# MIAN.net
KiCad netlist of a schematic drawn in Altium Designer
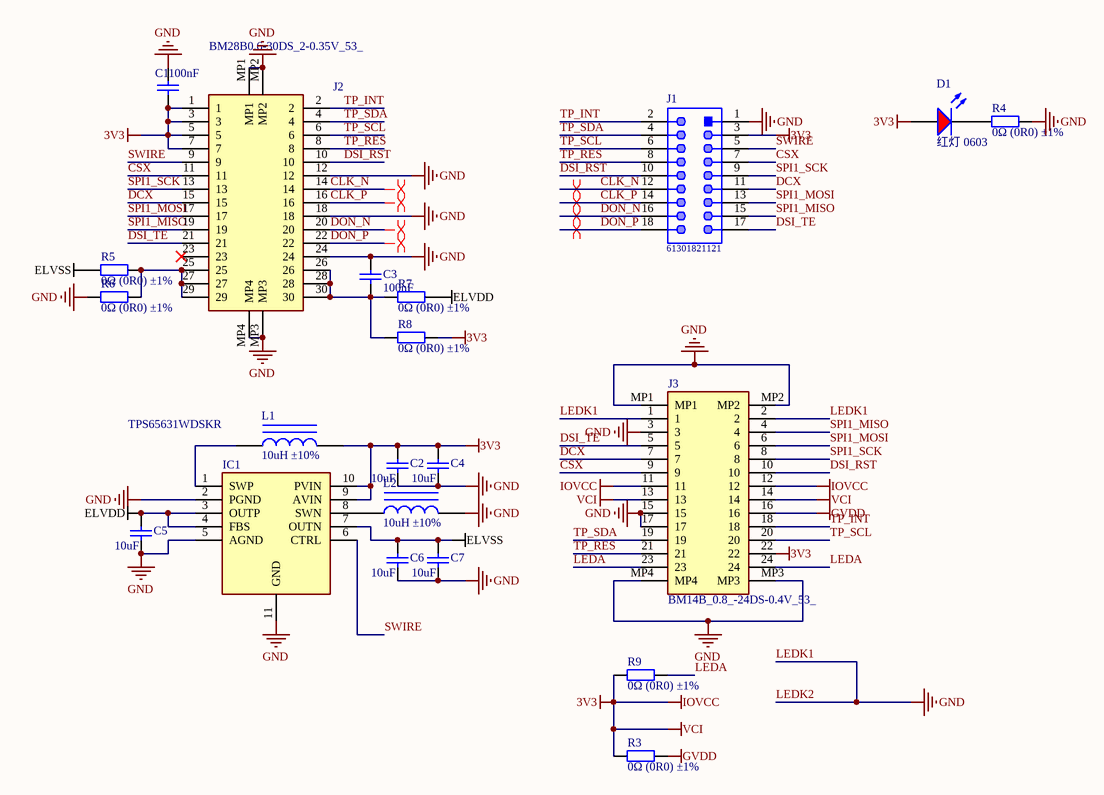
[diagram p0: MIAN.SchDoc]

(export (version "E")
  (design (tool "Eeschema 10.0.6"))
  (components
    (comp (ref "C1")
      (value "100nF")
      (footprint "0402_C")
      (description "Capacitor")
      (fields (field (name "PUBLISHER") "Altium Limited"))
      (libsource (lib "Miscellaneous Devices") (part "CAP"))
    )
    (comp (ref "C2")
      (value "10uF")
      (footprint "0402_C")
      (description "贴片电容")
      (libsource (lib "Miscellaneous Devices LC") (part "0402 10uF (106) 20% 6.3V"))
    )
    (comp (ref "C3")
      (value "100nF")
      (footprint "0402_C")
      (description "Capacitor")
      (fields (field (name "PUBLISHER") "Altium Limited"))
      (libsource (lib "Miscellaneous Devices") (part "CAP"))
    )
    (comp (ref "C4")
      (value "10uF")
      (footprint "0402_C")
      (description "贴片电容")
      (libsource (lib "Miscellaneous Devices LC") (part "0402 10uF (106) 20% 6.3V"))
    )
    (comp (ref "C5")
      (value "10uF")
      (footprint "0402_C")
      (description "贴片电容")
      (libsource (lib "Miscellaneous Devices LC") (part "0402 10uF (106) 20% 6.3V"))
    )
    (comp (ref "C6")
      (value "10uF")
      (footprint "0402_C")
      (description "贴片电容")
      (libsource (lib "Miscellaneous Devices LC") (part "0402 10uF (106) 20% 6.3V"))
    )
    (comp (ref "C7")
      (value "10uF")
      (footprint "0402_C")
      (description "贴片电容")
      (libsource (lib "Miscellaneous Devices LC") (part "0402 10uF (106) 20% 6.3V"))
    )
    (comp (ref "D1")
      (value "红灯 0603")
      (footprint "0603_LED_S1")
      (description "发光二极管")
      (libsource (lib "Miscellaneous Devices LC") (part "0603 红灯"))
    )
    (comp (ref "IC1")
      (value "TPS65631WDSKR")
      (footprint "SamacSys:SON50P250X250X80-11N-D")
      (description "Integrated Circuit")
      (fields (field (name "MOUSER PART NUMBER") "595-TPS65631WDSKR"))
      (libsource (lib "*") (part "TPS65631WDSKR"))
    )
    (comp (ref "J1")
      (value "61301821121")
      (footprint "61301821121")
      (description "THT Vertical Pin Header WR-PHD, Pitch 2.54 mm, Dual Row, 18 pins")
      (fields (field (name "MANUFACTURER") "Wurth Elektronik") (field (name "PUBLISHER") "WurthElektronik"))
      (libsource (lib "Altium Content Vault") (part "WE-CN-2P-M-R18"))
    )
    (comp (ref "J2")
      (value "BM28B0.6-30DS_2-0.35V_53_")
      (footprint "SamacSys:BM28B0630DS2035V53")
      (description "Connector")
      (fields
        (field (name "MANUFACTURER_PART_NUMBER") "BM28B0.6-30DS/2-0.35V(53)")
        (field (name "MOUSER PART NUMBER") "798-28B0630DS2035V53")
      )
      (libsource (lib "*") (part "BM28B0.6-30DS_2-0.35V_53_"))
    )
    (comp (ref "J3")
      (value "BM14B_0.8_-24DS-0.4V_53_")
      (footprint "SamacSys:BM14B0824DS04V53")
      (description "Connector")
      (fields
        (field (name "MANUFACTURER_PART_NUMBER") "BM14B(0.8)-24DS-0.4V(53)")
        (field (name "MOUSER PART NUMBER") "798-BM14B0824DS04V53")
      )
      (libsource (lib "*") (part "BM14B_0.8_-24DS-0.4V_53_"))
    )
    (comp (ref "L1")
      (value "10uH ±10%")
      (footprint "0805_L")
      (description "贴片电感")
      (libsource (lib "Miscellaneous Devices LC") (part "0805 10uH 10%"))
    )
    (comp (ref "L2")
      (value "10uH ±10%")
      (footprint "0805_L")
      (description "贴片电感")
      (libsource (lib "Miscellaneous Devices LC") (part "0805 10uH 10%"))
    )
    (comp (ref "R3")
      (value "0Ω (0R0) ±1%")
      (footprint "0402_R")
      (description "贴片电阻")
      (libsource (lib "Miscellaneous Devices LC") (part "0402 0Ω (0R0) 1%"))
    )
    (comp (ref "R4")
      (value "0Ω (0R0) ±1%")
      (footprint "0402_R")
      (description "贴片电阻")
      (libsource (lib "Miscellaneous Devices LC") (part "0402 0Ω (0R0) 1%"))
    )
    (comp (ref "R5")
      (value "0Ω (0R0) ±1%")
      (footprint "0402_R")
      (description "贴片电阻")
      (libsource (lib "Miscellaneous Devices LC") (part "0402 0Ω (0R0) 1%"))
    )
    (comp (ref "R6")
      (value "0Ω (0R0) ±1%")
      (footprint "0402_R")
      (description "贴片电阻")
      (libsource (lib "Miscellaneous Devices LC") (part "0402 0Ω (0R0) 1%"))
    )
    (comp (ref "R7")
      (value "0Ω (0R0) ±1%")
      (footprint "0402_R")
      (description "贴片电阻")
      (libsource (lib "Miscellaneous Devices LC") (part "0402 0Ω (0R0) 1%"))
    )
    (comp (ref "R8")
      (value "0Ω (0R0) ±1%")
      (footprint "0402_R")
      (description "贴片电阻")
      (libsource (lib "Miscellaneous Devices LC") (part "0402 0Ω (0R0) 1%"))
    )
    (comp (ref "R9")
      (value "0Ω (0R0) ±1%")
      (footprint "0402_R")
      (description "贴片电阻")
      (libsource (lib "Miscellaneous Devices LC") (part "0402 0Ω (0R0) 1%"))
    )
  )
  (nets
    (net (code "1") (name "/CLK_N") (class "Default")
      (node (ref "J1") (pin "12") (pinfunction "12_12") (pintype "passive"))
      (node (ref "J2") (pin "14") (pinfunction "14_14") (pintype "passive"))
    )
    (net (code "2") (name "/CLK_P") (class "Default")
      (node (ref "J1") (pin "14") (pinfunction "14_14") (pintype "passive"))
      (node (ref "J2") (pin "16") (pinfunction "16_16") (pintype "passive"))
    )
    (net (code "3") (name "/CSX") (class "Default")
      (node (ref "J1") (pin "7") (pinfunction "7_7") (pintype "passive"))
      (node (ref "J2") (pin "11") (pinfunction "11_11") (pintype "passive"))
      (node (ref "J3") (pin "9") (pinfunction "9_9") (pintype "passive"))
    )
    (net (code "4") (name "/DCX") (class "Default")
      (node (ref "J1") (pin "11") (pinfunction "11_11") (pintype "passive"))
      (node (ref "J2") (pin "15") (pinfunction "15_15") (pintype "passive"))
      (node (ref "J3") (pin "7") (pinfunction "7_7") (pintype "passive"))
    )
    (net (code "5") (name "/DON_N") (class "Default")
      (node (ref "J1") (pin "16") (pinfunction "16_16") (pintype "passive"))
      (node (ref "J2") (pin "20") (pinfunction "20_20") (pintype "passive"))
    )
    (net (code "6") (name "/DON_P") (class "Default")
      (node (ref "J1") (pin "18") (pinfunction "18_18") (pintype "passive"))
      (node (ref "J2") (pin "22") (pinfunction "22_22") (pintype "passive"))
    )
    (net (code "7") (name "/DSI_RST") (class "Default")
      (node (ref "J1") (pin "10") (pinfunction "10_10") (pintype "passive"))
      (node (ref "J2") (pin "10") (pinfunction "10_10") (pintype "passive"))
      (node (ref "J3") (pin "10") (pinfunction "10_10") (pintype "passive"))
    )
    (net (code "8") (name "/DSI_TE") (class "Default")
      (node (ref "J1") (pin "17") (pinfunction "17_17") (pintype "passive"))
      (node (ref "J2") (pin "21") (pinfunction "21_21") (pintype "passive"))
      (node (ref "J3") (pin "5") (pinfunction "5_5") (pintype "passive"))
    )
    (net (code "9") (name "/LEDA") (class "Default")
      (node (ref "J3") (pin "23") (pinfunction "23_23") (pintype "passive"))
      (node (ref "J3") (pin "24") (pinfunction "24_24") (pintype "passive"))
      (node (ref "R9") (pin "2") (pinfunction "2_2") (pintype "passive"))
    )
    (net (code "10") (name "/SPI1_MISO") (class "Default")
      (node (ref "J1") (pin "15") (pinfunction "15_15") (pintype "passive"))
      (node (ref "J2") (pin "19") (pinfunction "19_19") (pintype "passive"))
      (node (ref "J3") (pin "4") (pinfunction "4_4") (pintype "passive"))
    )
    (net (code "11") (name "/SPI1_MOSI") (class "Default")
      (node (ref "J1") (pin "13") (pinfunction "13_13") (pintype "passive"))
      (node (ref "J2") (pin "17") (pinfunction "17_17") (pintype "passive"))
      (node (ref "J3") (pin "6") (pinfunction "6_6") (pintype "passive"))
    )
    (net (code "12") (name "/SPI1_SCK") (class "Default")
      (node (ref "J1") (pin "9") (pinfunction "9_9") (pintype "passive"))
      (node (ref "J2") (pin "13") (pinfunction "13_13") (pintype "passive"))
      (node (ref "J3") (pin "8") (pinfunction "8_8") (pintype "passive"))
    )
    (net (code "13") (name "/SWIRE") (class "Default")
      (node (ref "IC1") (pin "6") (pinfunction "CTRL_6") (pintype "passive"))
      (node (ref "J1") (pin "5") (pinfunction "5_5") (pintype "passive"))
      (node (ref "J2") (pin "9") (pinfunction "9_9") (pintype "passive"))
    )
    (net (code "14") (name "/TP_INT") (class "Default")
      (node (ref "J1") (pin "2") (pinfunction "2_2") (pintype "passive"))
      (node (ref "J2") (pin "2") (pinfunction "2_2") (pintype "passive"))
      (node (ref "J3") (pin "18") (pinfunction "18_18") (pintype "passive"))
    )
    (net (code "15") (name "/TP_RES") (class "Default")
      (node (ref "J1") (pin "8") (pinfunction "8_8") (pintype "passive"))
      (node (ref "J2") (pin "8") (pinfunction "8_8") (pintype "passive"))
      (node (ref "J3") (pin "21") (pinfunction "21_21") (pintype "passive"))
    )
    (net (code "16") (name "/TP_SCL") (class "Default")
      (node (ref "J1") (pin "6") (pinfunction "6_6") (pintype "passive"))
      (node (ref "J2") (pin "6") (pinfunction "6_6") (pintype "passive"))
      (node (ref "J3") (pin "20") (pinfunction "20_20") (pintype "passive"))
    )
    (net (code "17") (name "/TP_SDA") (class "Default")
      (node (ref "J1") (pin "4") (pinfunction "4_4") (pintype "passive"))
      (node (ref "J2") (pin "4") (pinfunction "4_4") (pintype "passive"))
      (node (ref "J3") (pin "19") (pinfunction "19_19") (pintype "passive"))
    )
    (net (code "18") (name "3V3") (class "Default")
      (node (ref "C1") (pin "1") (pinfunction "1_1") (pintype "passive"))
      (node (ref "C2") (pin "2") (pinfunction "2_2") (pintype "passive"))
      (node (ref "C4") (pin "2") (pinfunction "2_2") (pintype "passive"))
      (node (ref "D1") (pin "A") (pinfunction "A_A") (pintype "passive"))
      (node (ref "IC1") (pin "10") (pinfunction "PVIN_10") (pintype "passive"))
      (node (ref "IC1") (pin "9") (pinfunction "AVIN_9") (pintype "passive"))
      (node (ref "J1") (pin "3") (pinfunction "3_3") (pintype "passive"))
      (node (ref "J2") (pin "1") (pinfunction "1_1") (pintype "passive"))
      (node (ref "J2") (pin "3") (pinfunction "3_3") (pintype "passive"))
      (node (ref "J2") (pin "5") (pinfunction "5_5") (pintype "passive"))
      (node (ref "J2") (pin "7") (pinfunction "7_7") (pintype "passive"))
      (node (ref "J3") (pin "11") (pinfunction "11_11") (pintype "passive"))
      (node (ref "J3") (pin "12") (pinfunction "12_12") (pintype "passive"))
      (node (ref "J3") (pin "13") (pinfunction "13_13") (pintype "passive"))
      (node (ref "J3") (pin "14") (pinfunction "14_14") (pintype "passive"))
      (node (ref "J3") (pin "22") (pinfunction "22_22") (pintype "passive"))
      (node (ref "L1") (pin "2") (pinfunction "2_2") (pintype "passive"))
      (node (ref "R3") (pin "1") (pinfunction "1_1") (pintype "passive"))
      (node (ref "R8") (pin "2") (pinfunction "2_2") (pintype "passive"))
      (node (ref "R9") (pin "1") (pinfunction "1_1") (pintype "passive"))
    )
    (net (code "19") (name "ELVDD") (class "Default")
      (node (ref "C5") (pin "2") (pinfunction "2_2") (pintype "passive"))
      (node (ref "IC1") (pin "3") (pinfunction "OUTP_3") (pintype "passive"))
      (node (ref "IC1") (pin "4") (pinfunction "FBS_4") (pintype "passive"))
      (node (ref "R7") (pin "2") (pinfunction "2_2") (pintype "passive"))
    )
    (net (code "20") (name "ELVSS") (class "Default")
      (node (ref "C6") (pin "2") (pinfunction "2_2") (pintype "passive"))
      (node (ref "C7") (pin "2") (pinfunction "2_2") (pintype "passive"))
      (node (ref "IC1") (pin "7") (pinfunction "OUTN_7") (pintype "passive"))
      (node (ref "R5") (pin "1") (pinfunction "1_1") (pintype "passive"))
    )
    (net (code "21") (name "GND") (class "Default")
      (node (ref "C1") (pin "2") (pinfunction "2_2") (pintype "passive"))
      (node (ref "C2") (pin "1") (pinfunction "1_1") (pintype "passive"))
      (node (ref "C3") (pin "1") (pinfunction "1_1") (pintype "passive"))
      (node (ref "C4") (pin "1") (pinfunction "1_1") (pintype "passive"))
      (node (ref "C5") (pin "1") (pinfunction "1_1") (pintype "passive"))
      (node (ref "C6") (pin "1") (pinfunction "1_1") (pintype "passive"))
      (node (ref "C7") (pin "1") (pinfunction "1_1") (pintype "passive"))
      (node (ref "IC1") (pin "11") (pinfunction "GND_11") (pintype "passive"))
      (node (ref "IC1") (pin "2") (pinfunction "PGND_2") (pintype "passive"))
      (node (ref "IC1") (pin "5") (pinfunction "AGND_5") (pintype "passive"))
      (node (ref "J1") (pin "1") (pinfunction "1_1") (pintype "passive"))
      (node (ref "J2") (pin "12") (pinfunction "12_12") (pintype "passive"))
      (node (ref "J2") (pin "18") (pinfunction "18_18") (pintype "passive"))
      (node (ref "J2") (pin "24") (pinfunction "24_24") (pintype "passive"))
      (node (ref "J2") (pin "MP1") (pinfunction "MP1_MP1") (pintype "passive"))
      (node (ref "J2") (pin "MP2") (pinfunction "MP2_MP2") (pintype "passive"))
      (node (ref "J2") (pin "MP3") (pinfunction "MP3_MP3") (pintype "passive"))
      (node (ref "J2") (pin "MP4") (pinfunction "MP4_MP4") (pintype "passive"))
      (node (ref "J3") (pin "1") (pinfunction "1_1") (pintype "passive"))
      (node (ref "J3") (pin "15") (pinfunction "15_15") (pintype "passive"))
      (node (ref "J3") (pin "17") (pinfunction "17_17") (pintype "passive"))
      (node (ref "J3") (pin "2") (pinfunction "2_2") (pintype "passive"))
      (node (ref "J3") (pin "3") (pinfunction "3_3") (pintype "passive"))
      (node (ref "J3") (pin "MP1") (pinfunction "MP1_MP1") (pintype "passive"))
      (node (ref "J3") (pin "MP2") (pinfunction "MP2_MP2") (pintype "passive"))
      (node (ref "J3") (pin "MP3") (pinfunction "MP3_MP3") (pintype "passive"))
      (node (ref "J3") (pin "MP4") (pinfunction "MP4_MP4") (pintype "passive"))
      (node (ref "L2") (pin "2") (pinfunction "2_2") (pintype "passive"))
      (node (ref "R4") (pin "2") (pinfunction "2_2") (pintype "passive"))
      (node (ref "R6") (pin "1") (pinfunction "1_1") (pintype "passive"))
    )
    (net (code "22") (name "GVDD") (class "Default")
      (node (ref "J3") (pin "16") (pinfunction "16_16") (pintype "passive"))
      (node (ref "R3") (pin "2") (pinfunction "2_2") (pintype "passive"))
    )
    (net (code "23") (name "Net-(C3-Pad2)") (class "Default")
      (node (ref "C3") (pin "2") (pinfunction "2_2") (pintype "passive"))
      (node (ref "J2") (pin "26") (pinfunction "26_26") (pintype "passive"))
      (node (ref "J2") (pin "28") (pinfunction "28_28") (pintype "passive"))
      (node (ref "J2") (pin "30") (pinfunction "30_30") (pintype "passive"))
      (node (ref "R7") (pin "1") (pinfunction "1_1") (pintype "passive"))
      (node (ref "R8") (pin "1") (pinfunction "1_1") (pintype "passive"))
    )
    (net (code "24") (name "Net-(D1-PadK)") (class "Default")
      (node (ref "D1") (pin "K") (pinfunction "K_K") (pintype "passive"))
      (node (ref "R4") (pin "1") (pinfunction "1_1") (pintype "passive"))
    )
    (net (code "25") (name "Net-(IC1-SWN)") (class "Default")
      (node (ref "IC1") (pin "8") (pinfunction "SWN_8") (pintype "passive"))
      (node (ref "L2") (pin "1") (pinfunction "1_1") (pintype "passive"))
    )
    (net (code "26") (name "Net-(IC1-SWP)") (class "Default")
      (node (ref "IC1") (pin "1") (pinfunction "SWP_1") (pintype "passive"))
      (node (ref "L1") (pin "1") (pinfunction "1_1") (pintype "passive"))
    )
    (net (code "27") (name "Net-(J2-Pad25)") (class "Default")
      (node (ref "J2") (pin "25") (pinfunction "25_25") (pintype "passive"))
      (node (ref "J2") (pin "27") (pinfunction "27_27") (pintype "passive"))
      (node (ref "J2") (pin "29") (pinfunction "29_29") (pintype "passive"))
      (node (ref "R5") (pin "2") (pinfunction "2_2") (pintype "passive"))
      (node (ref "R6") (pin "2") (pinfunction "2_2") (pintype "passive"))
    )
    (net (code "28") (name "unconnected-(J2-Pad23)") (class "Default")
      (node (ref "J2") (pin "23") (pinfunction "23_23") (pintype "passive+no_connect"))
    )
  )
)
